# Power.net
KiCad netlist of a schematic drawn in Altium Designer
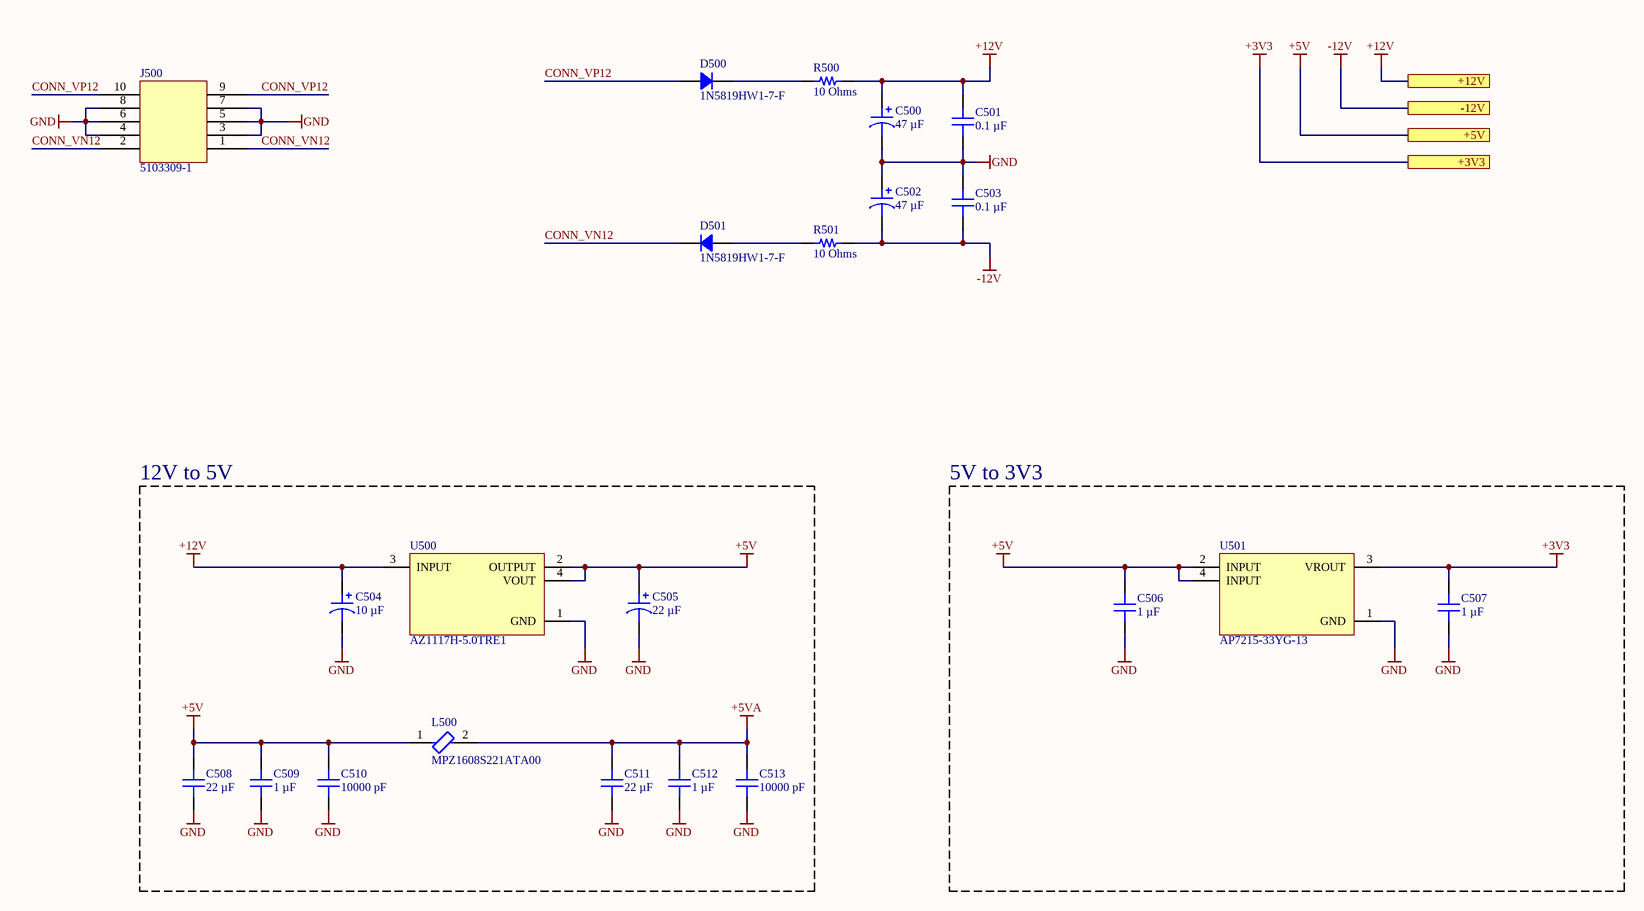
[diagram p0: Power.SchDoc]

(export (version "E")
  (design (tool "Eeschema 10.0.6"))
  (components
    (comp (ref "C500")
      (value "47 µF")
      (footprint "CAP ALSMD 6.6MM H8.0MM")
      (description "CAP ALUM 47UF 20% 35V SMD")
      (fields (field (name "PART NUMBER") "EXV476M035A9HAA") (field (name "MANUFACTURER") "KEMET"))
      (libsource (lib "Celestial Altium Library") (part "Polarised Capacitor"))
    )
    (comp (ref "C501")
      (value "0.1 µF")
      (footprint "CAP 0603_1608")
      (description "CAP CER 0.1UF 25V Y5V 0603")
      (fields (field (name "PART NUMBER") "CC0603MRY5V8BB104") (field (name "MANUFACTURER") "Yageo"))
      (libsource (lib "Celestial Altium Library") (part "Capacitor"))
    )
    (comp (ref "C502")
      (value "47 µF")
      (footprint "CAP ALSMD 6.6MM H8.0MM")
      (description "CAP ALUM 47UF 20% 35V SMD")
      (fields (field (name "PART NUMBER") "EXV476M035A9HAA") (field (name "MANUFACTURER") "KEMET"))
      (libsource (lib "Celestial Altium Library") (part "Polarised Capacitor"))
    )
    (comp (ref "C503")
      (value "0.1 µF")
      (footprint "CAP 0603_1608")
      (description "CAP CER 0.1UF 25V Y5V 0603")
      (fields (field (name "PART NUMBER") "CC0603MRY5V8BB104") (field (name "MANUFACTURER") "Yageo"))
      (libsource (lib "Celestial Altium Library") (part "Capacitor"))
    )
    (comp (ref "C504")
      (value "10 µF")
      (footprint "CAP ALSMD 4.3MM H5.4MM")
      (description "CAP ALUM 10UF 20% 16V SMD")
      (fields (field (name "PART NUMBER") "UWX1C100MCL1GB") (field (name "MANUFACTURER") "Nichicon"))
      (libsource (lib "Celestial Altium Library") (part "Polarised Capacitor"))
    )
    (comp (ref "C505")
      (value "22 µF")
      (footprint "CAP ALSMD 4.3MM H5.4MM")
      (description "CAP ALUM 22UF 20% 4V SMD")
      (fields (field (name "PART NUMBER") "UWT0G220MCL1GB") (field (name "MANUFACTURER") "Nichicon"))
      (libsource (lib "Celestial Altium Library") (part "Polarised Capacitor"))
    )
    (comp (ref "C506")
      (value "1 µF")
      (footprint "CAP 0603_1608")
      (description "CAP CER 1UF 10V X7R 0603")
      (fields (field (name "PART NUMBER") "CC0603KRX7R6BB105") (field (name "MANUFACTURER") "Yageo"))
      (libsource (lib "Celestial Altium Library") (part "Capacitor"))
    )
    (comp (ref "C507")
      (value "1 µF")
      (footprint "CAP 0603_1608")
      (description "CAP CER 1UF 10V X7R 0603")
      (fields (field (name "PART NUMBER") "CC0603KRX7R6BB105") (field (name "MANUFACTURER") "Yageo"))
      (libsource (lib "Celestial Altium Library") (part "Capacitor"))
    )
    (comp (ref "C508")
      (value "22 µF")
      (footprint "CAP 1206_3216 - 0.8MM")
      (description "CAP CER 22UF 6.3V X5R 1206")
      (fields (field (name "PART NUMBER") "CC1206MKX5R5BB226") (field (name "MANUFACTURER") "Yageo"))
      (libsource (lib "Celestial Altium Library") (part "Capacitor"))
    )
    (comp (ref "C509")
      (value "1 µF")
      (footprint "CAP 0603_1608")
      (description "CAP CER 1UF 10V X7R 0603")
      (fields (field (name "PART NUMBER") "CC0603KRX7R6BB105") (field (name "MANUFACTURER") "Yageo"))
      (libsource (lib "Celestial Altium Library") (part "Capacitor"))
    )
    (comp (ref "C510")
      (value "10000 pF")
      (footprint "CAP 0603_1608")
      (description "CAP CER 10000PF 50V X7R 0603")
      (fields (field (name "PART NUMBER") "CC0603JRX7R9BB103") (field (name "MANUFACTURER") "Yageo"))
      (libsource (lib "Celestial Altium Library") (part "Capacitor"))
    )
    (comp (ref "C511")
      (value "22 µF")
      (footprint "CAP 1206_3216 - 0.8MM")
      (description "CAP CER 22UF 6.3V X5R 1206")
      (fields (field (name "PART NUMBER") "CC1206MKX5R5BB226") (field (name "MANUFACTURER") "Yageo"))
      (libsource (lib "Celestial Altium Library") (part "Capacitor"))
    )
    (comp (ref "C512")
      (value "1 µF")
      (footprint "CAP 0603_1608")
      (description "CAP CER 1UF 10V X7R 0603")
      (fields (field (name "PART NUMBER") "CC0603KRX7R6BB105") (field (name "MANUFACTURER") "Yageo"))
      (libsource (lib "Celestial Altium Library") (part "Capacitor"))
    )
    (comp (ref "C513")
      (value "10000 pF")
      (footprint "CAP 0603_1608")
      (description "CAP CER 10000PF 50V X7R 0603")
      (fields (field (name "PART NUMBER") "CC0603JRX7R9BB103") (field (name "MANUFACTURER") "Yageo"))
      (libsource (lib "Celestial Altium Library") (part "Capacitor"))
    )
    (comp (ref "D500")
      (value "1N5819HW1-7-F")
      (footprint "SOD123F")
      (description "DIODE SBR 40V 1A SOD123F")
      (fields (field (name "MANUFACTURER") "Diodes Incorporated"))
      (libsource (lib "Celestial Altium Library") (part "Diode"))
    )
    (comp (ref "D501")
      (value "1N5819HW1-7-F")
      (footprint "SOD123F")
      (description "DIODE SBR 40V 1A SOD123F")
      (fields (field (name "MANUFACTURER") "Diodes Incorporated"))
      (libsource (lib "Celestial Altium Library") (part "Diode"))
    )
    (comp (ref "J500")
      (value "5103309-1")
      (footprint "SHROUDED_PIN_HEADER_2X5")
      (description "Headers & Wire Housings HDR VERT DOUBLE 10P low profile")
      (libsource (lib "LabratsSynthLib") (part "5103309-1"))
    )
    (comp (ref "L500")
      (value "MPZ1608S221ATA00")
      (footprint "FP-MPZ1608-0_8-MFG")
      (description "Power line Ferrite Bead 220Ω @ 100MHz 2.2A DCR 0.05Ω SMD 0603")
      (fields (field (name "TOLERANCE") "25%"))
      (libsource (lib "Altium Content Vault") (part "5f30dd21d616792df468990f7003faa"))
    )
    (comp (ref "R500")
      (value "10 Ohms")
      (footprint "RES 0603_1608")
      (description "RES 10 OHM 1% 1/10W 0603")
      (fields (field (name "PART NUMBER") "CRCW060310R0FKEAC") (field (name "MANUFACTURER") "Vishay Dale"))
      (libsource (lib "Celestial Altium Library") (part "Resistor"))
    )
    (comp (ref "R501")
      (value "10 Ohms")
      (footprint "RES 0603_1608")
      (description "RES 10 OHM 1% 1/10W 0603")
      (fields (field (name "PART NUMBER") "CRCW060310R0FKEAC") (field (name "MANUFACTURER") "Vishay Dale"))
      (libsource (lib "Celestial Altium Library") (part "Resistor"))
    )
    (comp (ref "U500")
      (value "AZ1117H-5.0TRE1")
      (footprint "FP-SOT223-MFG")
      (description "IC REG LINEAR 5V 1A SOT223")
      (libsource (lib "LabratsSynthLib") (part "AZ1117H-5.0TRE1"))
    )
    (comp (ref "U501")
      (value "AP7215-33YG-13")
      (footprint "SOT89-3L")
      (description "LDO Voltage Regulators SOT89-3L 3.3V/0.6A 250MV 3.3-5.5V 1.2V")
      (libsource (lib "LabratsSynthLib") (part "AP7215-33YG-13"))
    )
  )
  (nets
    (net (code "1") (name "+3V3") (class "Default")
      (node (ref "C507") (pin "2") (pinfunction "2_2") (pintype "passive"))
      (node (ref "U501") (pin "3") (pinfunction "VROUT_3") (pintype "power_in"))
    )
    (net (code "2") (name "+5V") (class "Default")
      (node (ref "C505") (pin "1") (pinfunction "1_1") (pintype "passive"))
      (node (ref "C506") (pin "2") (pinfunction "2_2") (pintype "passive"))
      (node (ref "C508") (pin "2") (pinfunction "2_2") (pintype "passive"))
      (node (ref "C509") (pin "2") (pinfunction "2_2") (pintype "passive"))
      (node (ref "C510") (pin "2") (pinfunction "2_2") (pintype "passive"))
      (node (ref "L500") (pin "1") (pinfunction "1_1") (pintype "passive"))
      (node (ref "U500") (pin "2") (pinfunction "OUTPUT_2") (pintype "power_in"))
      (node (ref "U500") (pin "4") (pinfunction "VOUT_4") (pintype "power_in"))
      (node (ref "U501") (pin "2") (pinfunction "INPUT_2") (pintype "power_in"))
      (node (ref "U501") (pin "4") (pinfunction "INPUT_4") (pintype "power_in"))
    )
    (net (code "3") (name "+5VA") (class "Default")
      (node (ref "C511") (pin "2") (pinfunction "2_2") (pintype "passive"))
      (node (ref "C512") (pin "2") (pinfunction "2_2") (pintype "passive"))
      (node (ref "C513") (pin "2") (pinfunction "2_2") (pintype "passive"))
      (node (ref "L500") (pin "2") (pinfunction "2_2") (pintype "passive"))
    )
    (net (code "4") (name "+12V") (class "Default")
      (node (ref "C500") (pin "1") (pinfunction "1_1") (pintype "passive"))
      (node (ref "C501") (pin "2") (pinfunction "2_2") (pintype "passive"))
      (node (ref "C504") (pin "1") (pinfunction "1_1") (pintype "passive"))
      (node (ref "R500") (pin "2") (pinfunction "2_2") (pintype "passive"))
      (node (ref "U500") (pin "3") (pinfunction "INPUT_3") (pintype "power_in"))
    )
    (net (code "5") (name "-12V") (class "Default")
      (node (ref "C502") (pin "2") (pinfunction "2_2") (pintype "passive"))
      (node (ref "C503") (pin "1") (pinfunction "1_1") (pintype "passive"))
      (node (ref "R501") (pin "2") (pinfunction "2_2") (pintype "passive"))
    )
    (net (code "6") (name "/CONN_VN12") (class "Default")
      (node (ref "D501") (pin "2") (pinfunction "2_2") (pintype "passive"))
      (node (ref "J500") (pin "1") (pinfunction "-12V_1") (pintype "passive"))
      (node (ref "J500") (pin "2") (pinfunction "-12V_2") (pintype "passive"))
    )
    (net (code "7") (name "/CONN_VP12") (class "Default")
      (node (ref "D500") (pin "1") (pinfunction "1_1") (pintype "passive"))
      (node (ref "J500") (pin "10") (pinfunction "+12V_10") (pintype "passive"))
      (node (ref "J500") (pin "9") (pinfunction "+12V_9") (pintype "passive"))
    )
    (net (code "8") (name "GND") (class "Default")
      (node (ref "C500") (pin "2") (pinfunction "2_2") (pintype "passive"))
      (node (ref "C501") (pin "1") (pinfunction "1_1") (pintype "passive"))
      (node (ref "C502") (pin "1") (pinfunction "1_1") (pintype "passive"))
      (node (ref "C503") (pin "2") (pinfunction "2_2") (pintype "passive"))
      (node (ref "C504") (pin "2") (pinfunction "2_2") (pintype "passive"))
      (node (ref "C505") (pin "2") (pinfunction "2_2") (pintype "passive"))
      (node (ref "C506") (pin "1") (pinfunction "1_1") (pintype "passive"))
      (node (ref "C507") (pin "1") (pinfunction "1_1") (pintype "passive"))
      (node (ref "C508") (pin "1") (pinfunction "1_1") (pintype "passive"))
      (node (ref "C509") (pin "1") (pinfunction "1_1") (pintype "passive"))
      (node (ref "C510") (pin "1") (pinfunction "1_1") (pintype "passive"))
      (node (ref "C511") (pin "1") (pinfunction "1_1") (pintype "passive"))
      (node (ref "C512") (pin "1") (pinfunction "1_1") (pintype "passive"))
      (node (ref "C513") (pin "1") (pinfunction "1_1") (pintype "passive"))
      (node (ref "J500") (pin "3") (pinfunction "GND_3") (pintype "passive"))
      (node (ref "J500") (pin "4") (pinfunction "GND_4") (pintype "passive"))
      (node (ref "J500") (pin "5") (pinfunction "GND_5") (pintype "passive"))
      (node (ref "J500") (pin "6") (pinfunction "GND_6") (pintype "passive"))
      (node (ref "J500") (pin "7") (pinfunction "GND_7") (pintype "passive"))
      (node (ref "J500") (pin "8") (pinfunction "GND_8") (pintype "passive"))
      (node (ref "U500") (pin "1") (pinfunction "GND_1") (pintype "power_in"))
      (node (ref "U501") (pin "1") (pinfunction "GND_1") (pintype "power_in"))
    )
    (net (code "9") (name "Net-(D500-Pad2)") (class "Default")
      (node (ref "D500") (pin "2") (pinfunction "2_2") (pintype "passive"))
      (node (ref "R500") (pin "1") (pinfunction "1_1") (pintype "passive"))
    )
    (net (code "10") (name "Net-(D501-Pad1)") (class "Default")
      (node (ref "D501") (pin "1") (pinfunction "1_1") (pintype "passive"))
      (node (ref "R501") (pin "1") (pinfunction "1_1") (pintype "passive"))
    )
  )
)
